# processor_board.net
KiCad netlist of a schematic drawn in EAGLE
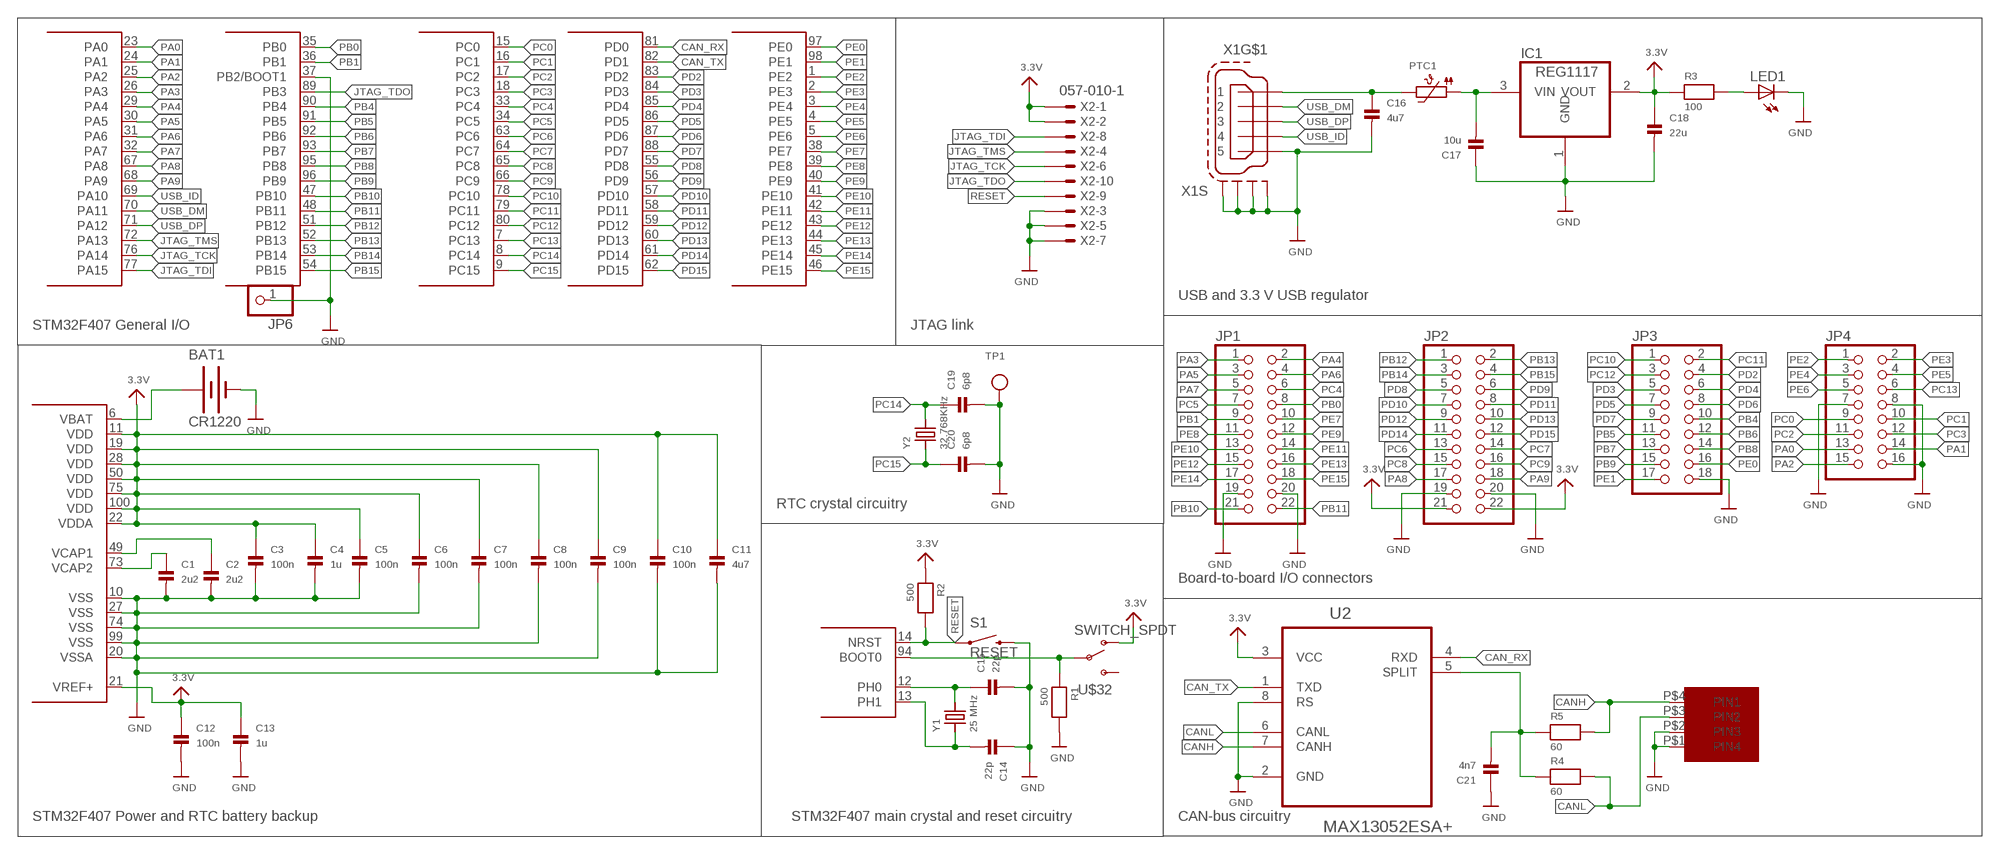
[diagram p0: schematic, sheet 1]

(export (version "E")
  (design (tool "Eeschema 10.0.6"))
  (components
    (comp (ref "BAT1")
      (value "CR1220")
      (footprint "eagle-import:BATTCON_12MM_PTH")
      (libsource (lib "eagle-import") (part "BATTERY12PTH"))
    )
    (comp (ref "C1")
      (value "2u2")
      (footprint "eagle-import:_0603MP")
      (libsource (lib "eagle-import") (part "CAP_CERAMIC_0603MP"))
    )
    (comp (ref "C2")
      (value "2u2")
      (footprint "eagle-import:_0603MP")
      (libsource (lib "eagle-import") (part "CAP_CERAMIC_0603MP"))
    )
    (comp (ref "C3")
      (value "100n")
      (footprint "eagle-import:_0603MP")
      (libsource (lib "eagle-import") (part "CAP_CERAMIC_0603MP"))
    )
    (comp (ref "C4")
      (value "1u")
      (footprint "eagle-import:_0603MP")
      (libsource (lib "eagle-import") (part "CAP_CERAMIC_0603MP"))
    )
    (comp (ref "C5")
      (value "100n")
      (footprint "eagle-import:_0603MP")
      (libsource (lib "eagle-import") (part "CAP_CERAMIC_0603MP"))
    )
    (comp (ref "C6")
      (value "100n")
      (footprint "eagle-import:_0603MP")
      (libsource (lib "eagle-import") (part "CAP_CERAMIC_0603MP"))
    )
    (comp (ref "C7")
      (value "100n")
      (footprint "eagle-import:_0603MP")
      (libsource (lib "eagle-import") (part "CAP_CERAMIC_0603MP"))
    )
    (comp (ref "C8")
      (value "100n")
      (footprint "eagle-import:_0603MP")
      (libsource (lib "eagle-import") (part "CAP_CERAMIC_0603MP"))
    )
    (comp (ref "C9")
      (value "100n")
      (footprint "eagle-import:_0603MP")
      (libsource (lib "eagle-import") (part "CAP_CERAMIC_0603MP"))
    )
    (comp (ref "C10")
      (value "100n")
      (footprint "eagle-import:_0603MP")
      (libsource (lib "eagle-import") (part "CAP_CERAMIC_0603MP"))
    )
    (comp (ref "C11")
      (value "4u7")
      (footprint "eagle-import:_0603MP")
      (libsource (lib "eagle-import") (part "CAP_CERAMIC_0603MP"))
    )
    (comp (ref "C12")
      (value "100n")
      (footprint "eagle-import:_0603MP")
      (libsource (lib "eagle-import") (part "CAP_CERAMIC_0603MP"))
    )
    (comp (ref "C13")
      (value "1u")
      (footprint "eagle-import:_0603MP")
      (libsource (lib "eagle-import") (part "CAP_CERAMIC_0603MP"))
    )
    (comp (ref "C14")
      (value "22p")
      (footprint "eagle-import:_0603MP")
      (libsource (lib "eagle-import") (part "CAP_CERAMIC_0603MP"))
    )
    (comp (ref "C15")
      (value "22p")
      (footprint "eagle-import:_0603MP")
      (libsource (lib "eagle-import") (part "CAP_CERAMIC_0603MP"))
    )
    (comp (ref "C16")
      (value "4u7")
      (footprint "eagle-import:_0603MP")
      (libsource (lib "eagle-import") (part "CAP_CERAMIC_0603MP"))
    )
    (comp (ref "C17")
      (value "10u")
      (footprint "eagle-import:_0603MP")
      (libsource (lib "eagle-import") (part "CAP_CERAMIC_0603MP"))
    )
    (comp (ref "C18")
      (value "22u")
      (footprint "eagle-import:_0603MP")
      (libsource (lib "eagle-import") (part "CAP_CERAMIC_0603MP"))
    )
    (comp (ref "C19")
      (value "6p8")
      (footprint "eagle-import:_0603MP")
      (libsource (lib "eagle-import") (part "CAP_CERAMIC_0603MP"))
    )
    (comp (ref "C20")
      (value "6p8")
      (footprint "eagle-import:_0603MP")
      (libsource (lib "eagle-import") (part "CAP_CERAMIC_0603MP"))
    )
    (comp (ref "C21")
      (value "4n7")
      (footprint "eagle-import:_0603")
      (libsource (lib "eagle-import") (part "CAP_CERAMIC_0603"))
    )
    (comp (ref "IC1")
      (value "REG1117")
      (footprint "eagle-import:SOT223")
      (libsource (lib "eagle-import") (part "REG1117"))
    )
    (comp (ref "JP1")
      (value "PINHD-2X11")
      (footprint "eagle-import:2X11")
      (libsource (lib "eagle-import") (part "PINHD-2X11"))
    )
    (comp (ref "JP2")
      (value "PINHD-2X11")
      (footprint "eagle-import:2X11")
      (libsource (lib "eagle-import") (part "PINHD-2X11"))
    )
    (comp (ref "JP3")
      (value "PINHD-2X9")
      (footprint "eagle-import:2X09")
      (libsource (lib "eagle-import") (part "PINHD-2X9"))
    )
    (comp (ref "JP4")
      (value "PINHD-2X8")
      (footprint "eagle-import:2X08")
      (libsource (lib "eagle-import") (part "PINHD-2X8"))
    )
    (comp (ref "JP6")
      (value "PINHD-1X1")
      (footprint "eagle-import:1X01")
      (libsource (lib "eagle-import") (part "PINHD-1X1"))
    )
    (comp (ref "LED1")
      (value "LEDCHIPLED_1206")
      (footprint "eagle-import:CHIPLED_1206")
      (libsource (lib "eagle-import") (part "LEDCHIPLED_1206"))
    )
    (comp (ref "PTC1")
      (value "PTC1206")
      (footprint "eagle-import:1206")
      (libsource (lib "eagle-import") (part "PTC1206"))
    )
    (comp (ref "R1")
      (value "500")
      (footprint "eagle-import:_0603MP")
      (libsource (lib "eagle-import") (part "RESISTOR_0603MP"))
    )
    (comp (ref "R2")
      (value "500")
      (footprint "eagle-import:_0603MP")
      (libsource (lib "eagle-import") (part "RESISTOR_0603MP"))
    )
    (comp (ref "R3")
      (value "100")
      (footprint "eagle-import:_0603MP")
      (libsource (lib "eagle-import") (part "RESISTOR_0603MP"))
    )
    (comp (ref "R4")
      (value "60")
      (footprint "eagle-import:_0603")
      (libsource (lib "eagle-import") (part "RESISTOR_0603"))
    )
    (comp (ref "R5")
      (value "60")
      (footprint "eagle-import:_0603")
      (libsource (lib "eagle-import") (part "RESISTOR_0603"))
    )
    (comp (ref "S1")
      (value "RESET")
      (footprint "eagle-import:TACTILE-SWITCH-1101NE")
      (libsource (lib "eagle-import") (part "SWITCH-MOMENTARY-2SMD-1101NE"))
    )
    (comp (ref "TP1")
      (value "TESTPOINT0.1\"")
      (footprint "eagle-import:1X01_ROUND")
      (libsource (lib "eagle-import") (part "TESTPOINT0.1{dblquote}"))
    )
    (comp (ref "U$23")
      (value "MICROFIT4")
      (footprint "eagle-import:43045-0400")
      (libsource (lib "eagle-import") (part "MICROFIT4"))
    )
    (comp (ref "U$32")
      (value "SWITCH_SPDT")
      (footprint "eagle-import:KPS-1290")
      (libsource (lib "eagle-import") (part "SWITCH_SPDT"))
    )
    (comp (ref "U1")
      (value "STM32F4-100")
      (footprint "eagle-import:SQFP-S-14X14-100")
      (libsource (lib "eagle-import") (part "STM32F4-100"))
    )
    (comp (ref "U2")
      (value "MAX13052ESA+")
      (footprint "eagle-import:SOIC127P600X175-8N")
      (libsource (lib "eagle-import") (part "MAX13052ESA+"))
    )
    (comp (ref "X1")
      (value "MINI-USB-SCHIELD-32005-201")
      (footprint "eagle-import:32005-201")
      (libsource (lib "eagle-import") (part "MINI-USB-SCHIELD-32005-201"))
    )
    (comp (ref "X2")
      (value "057-010-1")
      (footprint "eagle-import:057-010-1")
      (libsource (lib "eagle-import") (part "057-010-1"))
    )
    (comp (ref "Y1")
      (value "25 MHz")
      (footprint "eagle-import:CRYSTAL_2.5X2")
      (libsource (lib "eagle-import") (part "CRYSTAL2.5X2.0MM"))
    )
    (comp (ref "Y2")
      (value "32.768KHz")
      (footprint "eagle-import:CRYSTAL_CYL_2X6MM_SMT")
      (libsource (lib "eagle-import") (part "CRYSTAL32.768"))
    )
  )
  (nets
    (net (code "1") (name "3.3V") (class "Default")
      (node (ref "C10") (pin "1") (pinfunction "P$1_1") (pintype "passive"))
      (node (ref "C11") (pin "1") (pinfunction "P$1_1") (pintype "passive"))
      (node (ref "C12") (pin "1") (pinfunction "P$1_1") (pintype "passive"))
      (node (ref "C13") (pin "1") (pinfunction "P$1_1") (pintype "passive"))
      (node (ref "C18") (pin "1") (pinfunction "P$1_1") (pintype "passive"))
      (node (ref "C3") (pin "1") (pinfunction "P$1_1") (pintype "passive"))
      (node (ref "C4") (pin "1") (pinfunction "P$1_1") (pintype "passive"))
      (node (ref "C5") (pin "1") (pinfunction "P$1_1") (pintype "passive"))
      (node (ref "C6") (pin "1") (pinfunction "P$1_1") (pintype "passive"))
      (node (ref "C7") (pin "1") (pinfunction "P$1_1") (pintype "passive"))
      (node (ref "C8") (pin "1") (pinfunction "P$1_1") (pintype "passive"))
      (node (ref "C9") (pin "1") (pinfunction "P$1_1") (pintype "passive"))
      (node (ref "IC1") (pin "2") (pinfunction "VOUT_2") (pintype "output"))
      (node (ref "JP2") (pin "21") (pinfunction "21_21") (pintype "passive"))
      (node (ref "JP2") (pin "22") (pinfunction "22_22") (pintype "passive"))
      (node (ref "R2") (pin "1") (pinfunction "1_1") (pintype "passive"))
      (node (ref "R3") (pin "1") (pinfunction "1_1") (pintype "passive"))
      (node (ref "U$32") (pin "O") (pinfunction "O_O") (pintype "passive"))
      (node (ref "U1") (pin "100") (pinfunction "VDD_100") (pintype "power_in"))
      (node (ref "U1") (pin "11") (pinfunction "VDD_11") (pintype "power_in"))
      (node (ref "U1") (pin "19") (pinfunction "VDD_19") (pintype "power_in"))
      (node (ref "U1") (pin "21") (pinfunction "VREF+_21") (pintype "passive"))
      (node (ref "U1") (pin "22") (pinfunction "VDDA_22") (pintype "power_in"))
      (node (ref "U1") (pin "28") (pinfunction "VDD_28") (pintype "power_in"))
      (node (ref "U1") (pin "50") (pinfunction "VDD_50") (pintype "power_in"))
      (node (ref "U1") (pin "75") (pinfunction "VDD_75") (pintype "power_in"))
      (node (ref "U2") (pin "3") (pinfunction "VCC_3") (pintype "power_in"))
      (node (ref "X2") (pin "1") (pinfunction "S_1") (pintype "passive"))
      (node (ref "X2") (pin "2") (pinfunction "S_2") (pintype "passive"))
    )
    (net (code "2") (name "CANH") (class "Default")
      (node (ref "R5") (pin "2") (pinfunction "2_2") (pintype "passive"))
      (node (ref "U$23") (pin "P$4") (pinfunction "PIN1_P$4") (pintype "bidirectional"))
      (node (ref "U2") (pin "7") (pinfunction "CANH_7") (pintype "input"))
    )
    (net (code "3") (name "CANL") (class "Default")
      (node (ref "R4") (pin "2") (pinfunction "2_2") (pintype "passive"))
      (node (ref "U$23") (pin "P$3") (pinfunction "PIN2_P$3") (pintype "bidirectional"))
      (node (ref "U2") (pin "6") (pinfunction "CANL_6") (pintype "input"))
    )
    (net (code "4") (name "CAN_RX") (class "Default")
      (node (ref "U1") (pin "81") (pinfunction "PD0_81") (pintype "bidirectional"))
      (node (ref "U2") (pin "4") (pinfunction "RXD_4") (pintype "output"))
    )
    (net (code "5") (name "CAN_TX") (class "Default")
      (node (ref "U1") (pin "82") (pinfunction "PD1_82") (pintype "bidirectional"))
      (node (ref "U2") (pin "1") (pinfunction "TXD_1") (pintype "input"))
    )
    (net (code "6") (name "GND") (class "Default")
      (node (ref "BAT1") (pin "GND") (pinfunction "-_GND") (pintype "power_in"))
      (node (ref "C1") (pin "2") (pinfunction "P$2_2") (pintype "passive"))
      (node (ref "C10") (pin "2") (pinfunction "P$2_2") (pintype "passive"))
      (node (ref "C11") (pin "2") (pinfunction "P$2_2") (pintype "passive"))
      (node (ref "C12") (pin "2") (pinfunction "P$2_2") (pintype "passive"))
      (node (ref "C13") (pin "2") (pinfunction "P$2_2") (pintype "passive"))
      (node (ref "C14") (pin "1") (pinfunction "P$1_1") (pintype "passive"))
      (node (ref "C15") (pin "2") (pinfunction "P$2_2") (pintype "passive"))
      (node (ref "C16") (pin "2") (pinfunction "P$2_2") (pintype "passive"))
      (node (ref "C17") (pin "1") (pinfunction "P$1_1") (pintype "passive"))
      (node (ref "C18") (pin "2") (pinfunction "P$2_2") (pintype "passive"))
      (node (ref "C19") (pin "2") (pinfunction "P$2_2") (pintype "passive"))
      (node (ref "C2") (pin "2") (pinfunction "P$2_2") (pintype "passive"))
      (node (ref "C20") (pin "2") (pinfunction "P$2_2") (pintype "passive"))
      (node (ref "C21") (pin "1") (pinfunction "P$1_1") (pintype "passive"))
      (node (ref "C3") (pin "2") (pinfunction "P$2_2") (pintype "passive"))
      (node (ref "C4") (pin "2") (pinfunction "P$2_2") (pintype "passive"))
      (node (ref "C5") (pin "2") (pinfunction "P$2_2") (pintype "passive"))
      (node (ref "C6") (pin "2") (pinfunction "P$2_2") (pintype "passive"))
      (node (ref "C7") (pin "2") (pinfunction "P$2_2") (pintype "passive"))
      (node (ref "C8") (pin "2") (pinfunction "P$2_2") (pintype "passive"))
      (node (ref "C9") (pin "2") (pinfunction "P$2_2") (pintype "passive"))
      (node (ref "IC1") (pin "1") (pinfunction "GND_1") (pintype "power_in"))
      (node (ref "JP1") (pin "19") (pinfunction "19_19") (pintype "passive"))
      (node (ref "JP1") (pin "20") (pinfunction "20_20") (pintype "passive"))
      (node (ref "JP2") (pin "19") (pinfunction "19_19") (pintype "passive"))
      (node (ref "JP2") (pin "20") (pinfunction "20_20") (pintype "passive"))
      (node (ref "JP3") (pin "18") (pinfunction "18_18") (pintype "passive"))
      (node (ref "JP4") (pin "16") (pinfunction "16_16") (pintype "passive"))
      (node (ref "JP4") (pin "7") (pinfunction "7_7") (pintype "passive"))
      (node (ref "JP4") (pin "8") (pinfunction "8_8") (pintype "passive"))
      (node (ref "JP6") (pin "1") (pinfunction "1_1") (pintype "passive"))
      (node (ref "LED1") (pin "C") (pinfunction "C_C") (pintype "passive"))
      (node (ref "R1") (pin "2") (pinfunction "2_2") (pintype "passive"))
      (node (ref "S1") (pin "2") (pinfunction "2_2") (pintype "passive"))
      (node (ref "TP1") (pin "1") (pinfunction "P$1_1") (pintype "bidirectional"))
      (node (ref "U$23") (pin "P$1") (pinfunction "PIN4_P$1") (pintype "bidirectional"))
      (node (ref "U$23") (pin "P$2") (pinfunction "PIN3_P$2") (pintype "bidirectional"))
      (node (ref "U1") (pin "10") (pinfunction "VSS_10") (pintype "power_in"))
      (node (ref "U1") (pin "20") (pinfunction "VSSA_20") (pintype "power_in"))
      (node (ref "U1") (pin "27") (pinfunction "VSS_27") (pintype "power_in"))
      (node (ref "U1") (pin "37") (pinfunction "PB2/BOOT1_37") (pintype "bidirectional"))
      (node (ref "U1") (pin "74") (pinfunction "VSS_74") (pintype "power_in"))
      (node (ref "U1") (pin "99") (pinfunction "VSS_99") (pintype "power_in"))
      (node (ref "U2") (pin "2") (pinfunction "GND_2") (pintype "passive"))
      (node (ref "U2") (pin "8") (pinfunction "RS_8") (pintype "input"))
      (node (ref "X1") (pin "5") (pinfunction "5_5") (pintype "passive"))
      (node (ref "X1") (pin "M1") (pinfunction "S1_M1") (pintype "passive"))
      (node (ref "X1") (pin "M2") (pinfunction "S2_M2") (pintype "passive"))
      (node (ref "X1") (pin "M3") (pinfunction "S3_M3") (pintype "passive"))
      (node (ref "X1") (pin "M4") (pinfunction "S4_M4") (pintype "passive"))
      (node (ref "X2") (pin "3") (pinfunction "S_3") (pintype "passive"))
      (node (ref "X2") (pin "5") (pinfunction "S_5") (pintype "passive"))
      (node (ref "X2") (pin "7") (pinfunction "S_7") (pintype "passive"))
    )
    (net (code "7") (name "JTAG_TCK") (class "Default")
      (node (ref "U1") (pin "76") (pinfunction "PA14_76") (pintype "bidirectional"))
      (node (ref "X2") (pin "6") (pinfunction "S_6") (pintype "passive"))
    )
    (net (code "8") (name "JTAG_TDI") (class "Default")
      (node (ref "U1") (pin "77") (pinfunction "PA15_77") (pintype "bidirectional"))
      (node (ref "X2") (pin "8") (pinfunction "S_8") (pintype "passive"))
    )
    (net (code "9") (name "JTAG_TDO") (class "Default")
      (node (ref "U1") (pin "89") (pinfunction "PB3_89") (pintype "bidirectional"))
      (node (ref "X2") (pin "10") (pinfunction "S_10") (pintype "passive"))
    )
    (net (code "10") (name "JTAG_TMS") (class "Default")
      (node (ref "U1") (pin "72") (pinfunction "PA13_72") (pintype "bidirectional"))
      (node (ref "X2") (pin "4") (pinfunction "S_4") (pintype "passive"))
    )
    (net (code "11") (name "Net-(BAT1-+)") (class "Default")
      (node (ref "BAT1") (pin "VCC@1") (pinfunction "+_VCC@1") (pintype "power_in"))
      (node (ref "U1") (pin "6") (pinfunction "VBAT_6") (pintype "power_in"))
    )
    (net (code "12") (name "Net-(C1-P$1)") (class "Default")
      (node (ref "C1") (pin "1") (pinfunction "P$1_1") (pintype "passive"))
      (node (ref "U1") (pin "73") (pinfunction "VCAP2_73") (pintype "passive"))
    )
    (net (code "13") (name "Net-(C2-P$1)") (class "Default")
      (node (ref "C2") (pin "1") (pinfunction "P$1_1") (pintype "passive"))
      (node (ref "U1") (pin "49") (pinfunction "VCAP1_49") (pintype "passive"))
    )
    (net (code "14") (name "Net-(C14-P$2)") (class "Default")
      (node (ref "C14") (pin "2") (pinfunction "P$2_2") (pintype "passive"))
      (node (ref "U1") (pin "13") (pinfunction "PH1_13") (pintype "bidirectional"))
      (node (ref "Y1") (pin "1") (pinfunction "1_1") (pintype "passive"))
    )
    (net (code "15") (name "Net-(C15-P$1)") (class "Default")
      (node (ref "C15") (pin "1") (pinfunction "P$1_1") (pintype "passive"))
      (node (ref "U1") (pin "12") (pinfunction "PH0_12") (pintype "bidirectional"))
      (node (ref "Y1") (pin "3") (pinfunction "2_3") (pintype "passive"))
    )
    (net (code "16") (name "Net-(C16-P$1)") (class "Default")
      (node (ref "C16") (pin "1") (pinfunction "P$1_1") (pintype "passive"))
      (node (ref "PTC1") (pin "2") (pinfunction "2_2") (pintype "passive"))
      (node (ref "X1") (pin "1") (pinfunction "1_1") (pintype "passive"))
    )
    (net (code "17") (name "Net-(C17-P$2)") (class "Default")
      (node (ref "C17") (pin "2") (pinfunction "P$2_2") (pintype "passive"))
      (node (ref "IC1") (pin "3") (pinfunction "VIN_3") (pintype "input"))
      (node (ref "PTC1") (pin "1") (pinfunction "1_1") (pintype "passive"))
    )
    (net (code "18") (name "Net-(C21-P$2)") (class "Default")
      (node (ref "C21") (pin "2") (pinfunction "P$2_2") (pintype "passive"))
      (node (ref "R4") (pin "1") (pinfunction "1_1") (pintype "passive"))
      (node (ref "R5") (pin "1") (pinfunction "1_1") (pintype "passive"))
      (node (ref "U2") (pin "5") (pinfunction "SPLIT_5") (pintype "output"))
    )
    (net (code "19") (name "Net-(LED1-PadA)") (class "Default")
      (node (ref "LED1") (pin "A") (pinfunction "A_A") (pintype "passive"))
      (node (ref "R3") (pin "2") (pinfunction "2_2") (pintype "passive"))
    )
    (net (code "20") (name "Net-(U1G-BOOT0)") (class "Default")
      (node (ref "R1") (pin "1") (pinfunction "1_1") (pintype "passive"))
      (node (ref "U$32") (pin "P") (pinfunction "P_P") (pintype "passive"))
      (node (ref "U1") (pin "94") (pinfunction "BOOT0_94") (pintype "bidirectional"))
    )
    (net (code "21") (name "PA0") (class "Default")
      (node (ref "JP4") (pin "13") (pinfunction "13_13") (pintype "passive"))
      (node (ref "U1") (pin "23") (pinfunction "PA0_23") (pintype "bidirectional"))
    )
    (net (code "22") (name "PA1") (class "Default")
      (node (ref "JP4") (pin "14") (pinfunction "14_14") (pintype "passive"))
      (node (ref "U1") (pin "24") (pinfunction "PA1_24") (pintype "bidirectional"))
    )
    (net (code "23") (name "PA2") (class "Default")
      (node (ref "JP4") (pin "15") (pinfunction "15_15") (pintype "passive"))
      (node (ref "U1") (pin "25") (pinfunction "PA2_25") (pintype "bidirectional"))
    )
    (net (code "24") (name "PA3") (class "Default")
      (node (ref "JP1") (pin "1") (pinfunction "1_1") (pintype "passive"))
      (node (ref "U1") (pin "26") (pinfunction "PA3_26") (pintype "bidirectional"))
    )
    (net (code "25") (name "PA4") (class "Default")
      (node (ref "JP1") (pin "2") (pinfunction "2_2") (pintype "passive"))
      (node (ref "U1") (pin "29") (pinfunction "PA4_29") (pintype "bidirectional"))
    )
    (net (code "26") (name "PA5") (class "Default")
      (node (ref "JP1") (pin "3") (pinfunction "3_3") (pintype "passive"))
      (node (ref "U1") (pin "30") (pinfunction "PA5_30") (pintype "bidirectional"))
    )
    (net (code "27") (name "PA6") (class "Default")
      (node (ref "JP1") (pin "4") (pinfunction "4_4") (pintype "passive"))
      (node (ref "U1") (pin "31") (pinfunction "PA6_31") (pintype "bidirectional"))
    )
    (net (code "28") (name "PA7") (class "Default")
      (node (ref "JP1") (pin "5") (pinfunction "5_5") (pintype "passive"))
      (node (ref "U1") (pin "32") (pinfunction "PA7_32") (pintype "bidirectional"))
    )
    (net (code "29") (name "PA8") (class "Default")
      (node (ref "JP2") (pin "17") (pinfunction "17_17") (pintype "passive"))
      (node (ref "U1") (pin "67") (pinfunction "PA8_67") (pintype "bidirectional"))
    )
    (net (code "30") (name "PA9") (class "Default")
      (node (ref "JP2") (pin "18") (pinfunction "18_18") (pintype "passive"))
      (node (ref "U1") (pin "68") (pinfunction "PA9_68") (pintype "bidirectional"))
    )
    (net (code "31") (name "PB0") (class "Default")
      (node (ref "JP1") (pin "8") (pinfunction "8_8") (pintype "passive"))
      (node (ref "U1") (pin "35") (pinfunction "PB0_35") (pintype "bidirectional"))
    )
    (net (code "32") (name "PB1") (class "Default")
      (node (ref "JP1") (pin "9") (pinfunction "9_9") (pintype "passive"))
      (node (ref "U1") (pin "36") (pinfunction "PB1_36") (pintype "bidirectional"))
    )
    (net (code "33") (name "PB4") (class "Default")
      (node (ref "JP3") (pin "10") (pinfunction "10_10") (pintype "passive"))
      (node (ref "U1") (pin "90") (pinfunction "PB4_90") (pintype "bidirectional"))
    )
    (net (code "34") (name "PB5") (class "Default")
      (node (ref "JP3") (pin "11") (pinfunction "11_11") (pintype "passive"))
      (node (ref "U1") (pin "91") (pinfunction "PB5_91") (pintype "bidirectional"))
    )
    (net (code "35") (name "PB6") (class "Default")
      (node (ref "JP3") (pin "12") (pinfunction "12_12") (pintype "passive"))
      (node (ref "U1") (pin "92") (pinfunction "PB6_92") (pintype "bidirectional"))
    )
    (net (code "36") (name "PB7") (class "Default")
      (node (ref "JP3") (pin "13") (pinfunction "13_13") (pintype "passive"))
      (node (ref "U1") (pin "93") (pinfunction "PB7_93") (pintype "bidirectional"))
    )
    (net (code "37") (name "PB8") (class "Default")
      (node (ref "JP3") (pin "14") (pinfunction "14_14") (pintype "passive"))
      (node (ref "U1") (pin "95") (pinfunction "PB8_95") (pintype "bidirectional"))
    )
    (net (code "38") (name "PB9") (class "Default")
      (node (ref "JP3") (pin "15") (pinfunction "15_15") (pintype "passive"))
      (node (ref "U1") (pin "96") (pinfunction "PB9_96") (pintype "bidirectional"))
    )
    (net (code "39") (name "PB10") (class "Default")
      (node (ref "JP1") (pin "21") (pinfunction "21_21") (pintype "passive"))
      (node (ref "U1") (pin "47") (pinfunction "PB10_47") (pintype "bidirectional"))
    )
    (net (code "40") (name "PB11") (class "Default")
      (node (ref "JP1") (pin "22") (pinfunction "22_22") (pintype "passive"))
      (node (ref "U1") (pin "48") (pinfunction "PB11_48") (pintype "bidirectional"))
    )
    (net (code "41") (name "PB12") (class "Default")
      (node (ref "JP2") (pin "1") (pinfunction "1_1") (pintype "passive"))
      (node (ref "U1") (pin "51") (pinfunction "PB12_51") (pintype "bidirectional"))
    )
    (net (code "42") (name "PB13") (class "Default")
      (node (ref "JP2") (pin "2") (pinfunction "2_2") (pintype "passive"))
      (node (ref "U1") (pin "52") (pinfunction "PB13_52") (pintype "bidirectional"))
    )
    (net (code "43") (name "PB14") (class "Default")
      (node (ref "JP2") (pin "3") (pinfunction "3_3") (pintype "passive"))
      (node (ref "U1") (pin "53") (pinfunction "PB14_53") (pintype "bidirectional"))
    )
    (net (code "44") (name "PB15") (class "Default")
      (node (ref "JP2") (pin "4") (pinfunction "4_4") (pintype "passive"))
      (node (ref "U1") (pin "54") (pinfunction "PB15_54") (pintype "bidirectional"))
    )
    (net (code "45") (name "PC0") (class "Default")
      (node (ref "JP4") (pin "9") (pinfunction "9_9") (pintype "passive"))
      (node (ref "U1") (pin "15") (pinfunction "PC0_15") (pintype "bidirectional"))
    )
    (net (code "46") (name "PC1") (class "Default")
      (node (ref "JP4") (pin "10") (pinfunction "10_10") (pintype "passive"))
      (node (ref "U1") (pin "16") (pinfunction "PC1_16") (pintype "bidirectional"))
    )
    (net (code "47") (name "PC2") (class "Default")
      (node (ref "JP4") (pin "11") (pinfunction "11_11") (pintype "passive"))
      (node (ref "U1") (pin "17") (pinfunction "PC2_17") (pintype "bidirectional"))
    )
    (net (code "48") (name "PC3") (class "Default")
      (node (ref "JP4") (pin "12") (pinfunction "12_12") (pintype "passive"))
      (node (ref "U1") (pin "18") (pinfunction "PC3_18") (pintype "bidirectional"))
    )
    (net (code "49") (name "PC4") (class "Default")
      (node (ref "JP1") (pin "6") (pinfunction "6_6") (pintype "passive"))
      (node (ref "U1") (pin "33") (pinfunction "PC4_33") (pintype "bidirectional"))
    )
    (net (code "50") (name "PC5") (class "Default")
      (node (ref "JP1") (pin "7") (pinfunction "7_7") (pintype "passive"))
      (node (ref "U1") (pin "34") (pinfunction "PC5_34") (pintype "bidirectional"))
    )
    (net (code "51") (name "PC6") (class "Default")
      (node (ref "JP2") (pin "13") (pinfunction "13_13") (pintype "passive"))
      (node (ref "U1") (pin "63") (pinfunction "PC6_63") (pintype "bidirectional"))
    )
    (net (code "52") (name "PC7") (class "Default")
      (node (ref "JP2") (pin "14") (pinfunction "14_14") (pintype "passive"))
      (node (ref "U1") (pin "64") (pinfunction "PC7_64") (pintype "bidirectional"))
    )
    (net (code "53") (name "PC8") (class "Default")
      (node (ref "JP2") (pin "15") (pinfunction "15_15") (pintype "passive"))
      (node (ref "U1") (pin "65") (pinfunction "PC8_65") (pintype "bidirectional"))
    )
    (net (code "54") (name "PC9") (class "Default")
      (node (ref "JP2") (pin "16") (pinfunction "16_16") (pintype "passive"))
      (node (ref "U1") (pin "66") (pinfunction "PC9_66") (pintype "bidirectional"))
    )
    (net (code "55") (name "PC10") (class "Default")
      (node (ref "JP3") (pin "1") (pinfunction "1_1") (pintype "passive"))
      (node (ref "U1") (pin "78") (pinfunction "PC10_78") (pintype "bidirectional"))
    )
    (net (code "56") (name "PC11") (class "Default")
      (node (ref "JP3") (pin "2") (pinfunction "2_2") (pintype "passive"))
      (node (ref "U1") (pin "79") (pinfunction "PC11_79") (pintype "bidirectional"))
    )
    (net (code "57") (name "PC12") (class "Default")
      (node (ref "JP3") (pin "3") (pinfunction "3_3") (pintype "passive"))
      (node (ref "U1") (pin "80") (pinfunction "PC12_80") (pintype "bidirectional"))
    )
    (net (code "58") (name "PC13") (class "Default")
      (node (ref "JP4") (pin "6") (pinfunction "6_6") (pintype "passive"))
      (node (ref "U1") (pin "7") (pinfunction "PC13_7") (pintype "bidirectional"))
    )
    (net (code "59") (name "PC14") (class "Default")
      (node (ref "C19") (pin "1") (pinfunction "P$1_1") (pintype "passive"))
      (node (ref "U1") (pin "8") (pinfunction "PC14_8") (pintype "bidirectional"))
      (node (ref "Y2") (pin "2") (pinfunction "2_2") (pintype "passive"))
    )
    (net (code "60") (name "PC15") (class "Default")
      (node (ref "C20") (pin "1") (pinfunction "P$1_1") (pintype "passive"))
      (node (ref "U1") (pin "9") (pinfunction "PC15_9") (pintype "bidirectional"))
      (node (ref "Y2") (pin "1") (pinfunction "1_1") (pintype "passive"))
    )
    (net (code "61") (name "PD2") (class "Default")
      (node (ref "JP3") (pin "4") (pinfunction "4_4") (pintype "passive"))
      (node (ref "U1") (pin "83") (pinfunction "PD2_83") (pintype "bidirectional"))
    )
    (net (code "62") (name "PD3") (class "Default")
      (node (ref "JP3") (pin "5") (pinfunction "5_5") (pintype "passive"))
      (node (ref "U1") (pin "84") (pinfunction "PD3_84") (pintype "bidirectional"))
    )
    (net (code "63") (name "PD4") (class "Default")
      (node (ref "JP3") (pin "6") (pinfunction "6_6") (pintype "passive"))
      (node (ref "U1") (pin "85") (pinfunction "PD4_85") (pintype "bidirectional"))
    )
    (net (code "64") (name "PD5") (class "Default")
      (node (ref "JP3") (pin "7") (pinfunction "7_7") (pintype "passive"))
      (node (ref "U1") (pin "86") (pinfunction "PD5_86") (pintype "bidirectional"))
    )
    (net (code "65") (name "PD6") (class "Default")
      (node (ref "JP3") (pin "8") (pinfunction "8_8") (pintype "passive"))
      (node (ref "U1") (pin "87") (pinfunction "PD6_87") (pintype "bidirectional"))
    )
    (net (code "66") (name "PD7") (class "Default")
      (node (ref "JP3") (pin "9") (pinfunction "9_9") (pintype "passive"))
      (node (ref "U1") (pin "88") (pinfunction "PD7_88") (pintype "bidirectional"))
    )
    (net (code "67") (name "PD8") (class "Default")
      (node (ref "JP2") (pin "5") (pinfunction "5_5") (pintype "passive"))
      (node (ref "U1") (pin "55") (pinfunction "PD8_55") (pintype "bidirectional"))
    )
    (net (code "68") (name "PD9") (class "Default")
      (node (ref "JP2") (pin "6") (pinfunction "6_6") (pintype "passive"))
      (node (ref "U1") (pin "56") (pinfunction "PD9_56") (pintype "bidirectional"))
    )
    (net (code "69") (name "PD10") (class "Default")
      (node (ref "JP2") (pin "7") (pinfunction "7_7") (pintype "passive"))
      (node (ref "U1") (pin "57") (pinfunction "PD10_57") (pintype "bidirectional"))
    )
    (net (code "70") (name "PD11") (class "Default")
      (node (ref "JP2") (pin "8") (pinfunction "8_8") (pintype "passive"))
      (node (ref "U1") (pin "58") (pinfunction "PD11_58") (pintype "bidirectional"))
    )
    (net (code "71") (name "PD12") (class "Default")
      (node (ref "JP2") (pin "9") (pinfunction "9_9") (pintype "passive"))
      (node (ref "U1") (pin "59") (pinfunction "PD12_59") (pintype "bidirectional"))
    )
    (net (code "72") (name "PD13") (class "Default")
      (node (ref "JP2") (pin "10") (pinfunction "10_10") (pintype "passive"))
      (node (ref "U1") (pin "60") (pinfunction "PD13_60") (pintype "bidirectional"))
    )
    (net (code "73") (name "PD14") (class "Default")
      (node (ref "JP2") (pin "11") (pinfunction "11_11") (pintype "passive"))
      (node (ref "U1") (pin "61") (pinfunction "PD14_61") (pintype "bidirectional"))
    )
    (net (code "74") (name "PD15") (class "Default")
      (node (ref "JP2") (pin "12") (pinfunction "12_12") (pintype "passive"))
      (node (ref "U1") (pin "62") (pinfunction "PD15_62") (pintype "bidirectional"))
    )
    (net (code "75") (name "PE0") (class "Default")
      (node (ref "JP3") (pin "16") (pinfunction "16_16") (pintype "passive"))
      (node (ref "U1") (pin "97") (pinfunction "PE0_97") (pintype "bidirectional"))
    )
    (net (code "76") (name "PE1") (class "Default")
      (node (ref "JP3") (pin "17") (pinfunction "17_17") (pintype "passive"))
      (node (ref "U1") (pin "98") (pinfunction "PE1_98") (pintype "bidirectional"))
    )
    (net (code "77") (name "PE2") (class "Default")
      (node (ref "JP4") (pin "1") (pinfunction "1_1") (pintype "passive"))
      (node (ref "U1") (pin "1") (pinfunction "PE2_1") (pintype "bidirectional"))
    )
    (net (code "78") (name "PE3") (class "Default")
      (node (ref "JP4") (pin "2") (pinfunction "2_2") (pintype "passive"))
      (node (ref "U1") (pin "2") (pinfunction "PE3_2") (pintype "bidirectional"))
    )
    (net (code "79") (name "PE4") (class "Default")
      (node (ref "JP4") (pin "3") (pinfunction "3_3") (pintype "passive"))
      (node (ref "U1") (pin "3") (pinfunction "PE4_3") (pintype "bidirectional"))
    )
    (net (code "80") (name "PE5") (class "Default")
      (node (ref "JP4") (pin "4") (pinfunction "4_4") (pintype "passive"))
      (node (ref "U1") (pin "4") (pinfunction "PE5_4") (pintype "bidirectional"))
    )
    (net (code "81") (name "PE6") (class "Default")
      (node (ref "JP4") (pin "5") (pinfunction "5_5") (pintype "passive"))
      (node (ref "U1") (pin "5") (pinfunction "PE6_5") (pintype "bidirectional"))
    )
    (net (code "82") (name "PE7") (class "Default")
      (node (ref "JP1") (pin "10") (pinfunction "10_10") (pintype "passive"))
      (node (ref "U1") (pin "38") (pinfunction "PE7_38") (pintype "bidirectional"))
    )
    (net (code "83") (name "PE8") (class "Default")
      (node (ref "JP1") (pin "11") (pinfunction "11_11") (pintype "passive"))
      (node (ref "U1") (pin "39") (pinfunction "PE8_39") (pintype "bidirectional"))
    )
    (net (code "84") (name "PE9") (class "Default")
      (node (ref "JP1") (pin "12") (pinfunction "12_12") (pintype "passive"))
      (node (ref "U1") (pin "40") (pinfunction "PE9_40") (pintype "bidirectional"))
    )
    (net (code "85") (name "PE10") (class "Default")
      (node (ref "JP1") (pin "13") (pinfunction "13_13") (pintype "passive"))
      (node (ref "U1") (pin "41") (pinfunction "PE10_41") (pintype "bidirectional"))
    )
    (net (code "86") (name "PE11") (class "Default")
      (node (ref "JP1") (pin "14") (pinfunction "14_14") (pintype "passive"))
      (node (ref "U1") (pin "42") (pinfunction "PE11_42") (pintype "bidirectional"))
    )
    (net (code "87") (name "PE12") (class "Default")
      (node (ref "JP1") (pin "15") (pinfunction "15_15") (pintype "passive"))
      (node (ref "U1") (pin "43") (pinfunction "PE12_43") (pintype "bidirectional"))
    )
    (net (code "88") (name "PE13") (class "Default")
      (node (ref "JP1") (pin "16") (pinfunction "16_16") (pintype "passive"))
      (node (ref "U1") (pin "44") (pinfunction "PE13_44") (pintype "bidirectional"))
    )
    (net (code "89") (name "PE14") (class "Default")
      (node (ref "JP1") (pin "17") (pinfunction "17_17") (pintype "passive"))
      (node (ref "U1") (pin "45") (pinfunction "PE14_45") (pintype "bidirectional"))
    )
    (net (code "90") (name "PE15") (class "Default")
      (node (ref "JP1") (pin "18") (pinfunction "18_18") (pintype "passive"))
      (node (ref "U1") (pin "46") (pinfunction "PE15_46") (pintype "bidirectional"))
    )
    (net (code "91") (name "RESET") (class "Default")
      (node (ref "R2") (pin "2") (pinfunction "2_2") (pintype "passive"))
      (node (ref "S1") (pin "1") (pinfunction "1_1") (pintype "passive"))
      (node (ref "U1") (pin "14") (pinfunction "NRST_14") (pintype "bidirectional"))
      (node (ref "X2") (pin "9") (pinfunction "S_9") (pintype "passive"))
    )
    (net (code "92") (name "USB_DM") (class "Default")
      (node (ref "U1") (pin "70") (pinfunction "PA11_70") (pintype "bidirectional"))
      (node (ref "X1") (pin "2") (pinfunction "2_2") (pintype "passive"))
    )
    (net (code "93") (name "USB_DP") (class "Default")
      (node (ref "U1") (pin "71") (pinfunction "PA12_71") (pintype "bidirectional"))
      (node (ref "X1") (pin "3") (pinfunction "3_3") (pintype "passive"))
    )
    (net (code "94") (name "USB_ID") (class "Default")
      (node (ref "U1") (pin "69") (pinfunction "PA10_69") (pintype "bidirectional"))
      (node (ref "X1") (pin "4") (pinfunction "4_4") (pintype "passive"))
    )
    (net (code "95") (name "unconnected-(U$32-PadS)") (class "Default")
      (node (ref "U$32") (pin "S") (pinfunction "S_S") (pintype "passive"))
    )
  )
)
